# 02_-_Discriminators.net
KiCad netlist of a schematic drawn in Altium Designer
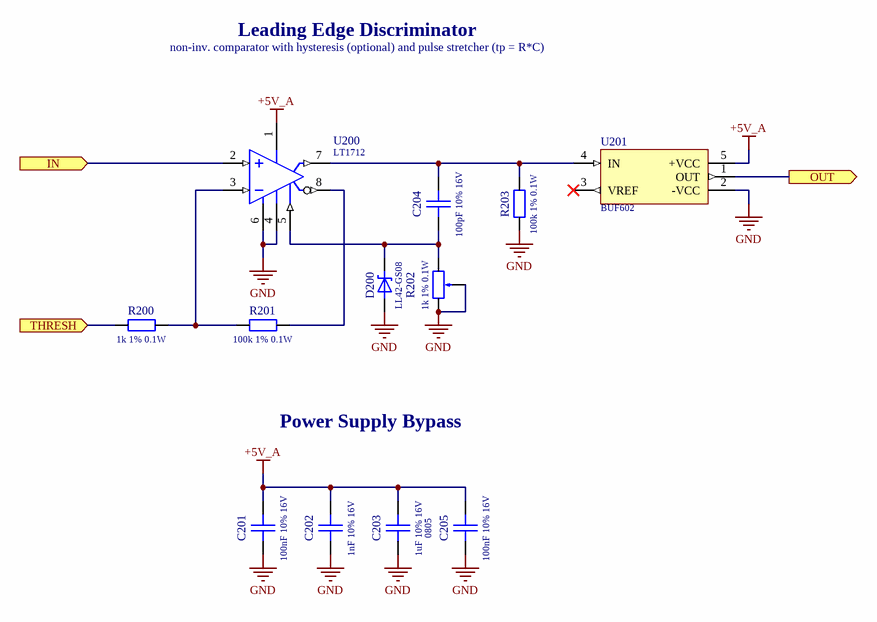
[diagram p0: [02] - Discriminators.SchDoc]

(export (version "E")
  (design (tool "Eeschema 10.0.6"))
  (components
    (comp (ref "C201")
      (value "100nF 10% 16V")
      (footprint "0603_CAP")
      (description "Simple generic capacitor.")
      (libsource (lib "CustomComponents") (part "Capacitor"))
    )
    (comp (ref "C202")
      (value "1nF 10% 16V")
      (footprint "0603_CAP")
      (description "Simple generic capacitor.")
      (libsource (lib "CustomComponents") (part "Capacitor"))
    )
    (comp (ref "C203")
      (value "1uF 10% 16V")
      (footprint "0805_CAP")
      (description "Simple generic capacitor.")
      (fields (field (name "PACKAGEREFERENCE") "0805"))
      (libsource (lib "CustomComponents") (part "Capacitor"))
    )
    (comp (ref "C204")
      (value "100pF 10% 16V")
      (footprint "0603_CAP")
      (description "Simple generic capacitor.")
      (libsource (lib "CustomComponents") (part "Capacitor"))
    )
    (comp (ref "C205")
      (value "100nF 10% 16V")
      (footprint "0603_CAP")
      (description "Simple generic capacitor.")
      (libsource (lib "CustomComponents") (part "Capacitor"))
    )
    (comp (ref "D200")
      (value "LL42-GS08")
      (footprint "MiniMELF")
      (description "Simple schottky diode.")
      (fields (field (name "MANUFACTURER") "Vishay"))
      (libsource (lib "CustomComponents") (part "Schottky Diode"))
    )
    (comp (ref "R200")
      (value "1k 1% 0.1W")
      (footprint "0603_RES")
      (description "Simple generic resistor.")
      (libsource (lib "CustomComponents") (part "Resistor"))
    )
    (comp (ref "R201")
      (value "100k 1% 0.1W")
      (footprint "0603_RES")
      (description "Simple generic resistor.")
      (libsource (lib "CustomComponents") (part "Resistor"))
    )
    (comp (ref "R202")
      (value "1k 1% 0.1W")
      (footprint "3224W")
      (description "Simple generic potentiometer.")
      (libsource (lib "CustomComponents") (part "Potentiometer"))
    )
    (comp (ref "R203")
      (value "100k 1% 0.1W")
      (footprint "0603_RES")
      (description "Simple generic resistor.")
      (libsource (lib "CustomComponents") (part "Resistor"))
    )
    (comp (ref "U200")
      (value "LT1712")
      (footprint "MSOP-8")
      (description "Single/Dual 4.5ns, 3V/5V/±5V, Rail-to-Rail Comparators")
      (fields (field (name "MANUFACTURER") "Analog Devices") (field (name "PARTNUMBER") "LT1712CGN"))
      (libsource (lib "CustomComponents") (part "LT1712"))
    )
    (comp (ref "U201")
      (value "BUF602")
      (footprint "SOT-23-5")
      (description "High-Speed, Closed-Loop Buffer.")
      (fields (field (name "MANUFACTURER") "Texas Instruments") (field (name "PARTNUMBER") "BUF602IDBVT"))
      (libsource (lib "CustomComponents") (part "BUF602"))
    )
  )
  (nets
    (net (code "1") (name "+5V_A") (class "Default")
      (node (ref "C201") (pin "2") (pinfunction "2_2") (pintype "passive"))
      (node (ref "C202") (pin "2") (pinfunction "2_2") (pintype "passive"))
      (node (ref "C203") (pin "2") (pinfunction "2_2") (pintype "passive"))
      (node (ref "C205") (pin "2") (pinfunction "2_2") (pintype "passive"))
      (node (ref "U200") (pin "1") (pinfunction "+V_1") (pintype "power_in"))
      (node (ref "U201") (pin "5") (pinfunction "+VCC_5") (pintype "power_in"))
    )
    (net (code "2") (name "/IN") (class "Default")
      (node (ref "U200") (pin "2") (pinfunction "+IN_2") (pintype "input"))
    )
    (net (code "3") (name "/OUT") (class "Default")
      (node (ref "U201") (pin "1") (pinfunction "OUT_1") (pintype "output"))
    )
    (net (code "4") (name "/THRESH") (class "Default")
      (node (ref "R200") (pin "2") (pinfunction "2_2") (pintype "passive"))
    )
    (net (code "5") (name "GND") (class "Default")
      (node (ref "C201") (pin "1") (pinfunction "1_1") (pintype "passive"))
      (node (ref "C202") (pin "1") (pinfunction "1_1") (pintype "passive"))
      (node (ref "C203") (pin "1") (pinfunction "1_1") (pintype "passive"))
      (node (ref "C205") (pin "1") (pinfunction "1_1") (pintype "passive"))
      (node (ref "D200") (pin "2") (pinfunction "A_2") (pintype "passive"))
      (node (ref "R202") (pin "1") (pinfunction "CCW_1") (pintype "passive"))
      (node (ref "R202") (pin "2") (pinfunction "WIPER_2") (pintype "passive"))
      (node (ref "R203") (pin "2") (pinfunction "2_2") (pintype "passive"))
      (node (ref "U200") (pin "4") (pinfunction "-V_4") (pintype "power_in"))
      (node (ref "U200") (pin "6") (pinfunction "GND_6") (pintype "power_in"))
      (node (ref "U201") (pin "2") (pinfunction "-VCC_2") (pintype "power_in"))
    )
    (net (code "6") (name "Net-(D200-K)") (class "Default")
      (node (ref "C204") (pin "1") (pinfunction "1_1") (pintype "passive"))
      (node (ref "D200") (pin "1") (pinfunction "K_1") (pintype "passive"))
      (node (ref "R202") (pin "3") (pinfunction "CW_3") (pintype "passive"))
      (node (ref "U200") (pin "5") (pinfunction "LE_5") (pintype "input"))
    )
    (net (code "7") (name "Net-(U200--IN)") (class "Default")
      (node (ref "R200") (pin "1") (pinfunction "1_1") (pintype "passive"))
      (node (ref "R201") (pin "2") (pinfunction "2_2") (pintype "passive"))
      (node (ref "U200") (pin "3") (pinfunction "-IN_3") (pintype "input"))
    )
    (net (code "8") (name "Net-(U200-Q)") (class "Default")
      (node (ref "C204") (pin "2") (pinfunction "2_2") (pintype "passive"))
      (node (ref "R203") (pin "1") (pinfunction "1_1") (pintype "passive"))
      (node (ref "U200") (pin "7") (pinfunction "Q_7") (pintype "output"))
      (node (ref "U201") (pin "4") (pinfunction "IN_4") (pintype "input"))
    )
    (net (code "9") (name "Net-(U200-~{Q})") (class "Default")
      (node (ref "R201") (pin "1") (pinfunction "1_1") (pintype "passive"))
      (node (ref "U200") (pin "8") (pinfunction "~{Q}_8") (pintype "output"))
    )
    (net (code "10") (name "unconnected-(U201-VREF-Pad3)") (class "Default")
      (node (ref "U201") (pin "3") (pinfunction "VREF_3") (pintype "output+no_connect"))
    )
  )
)
